# LPCB234_-_CAN.net
KiCad netlist of a schematic drawn in Altium Designer
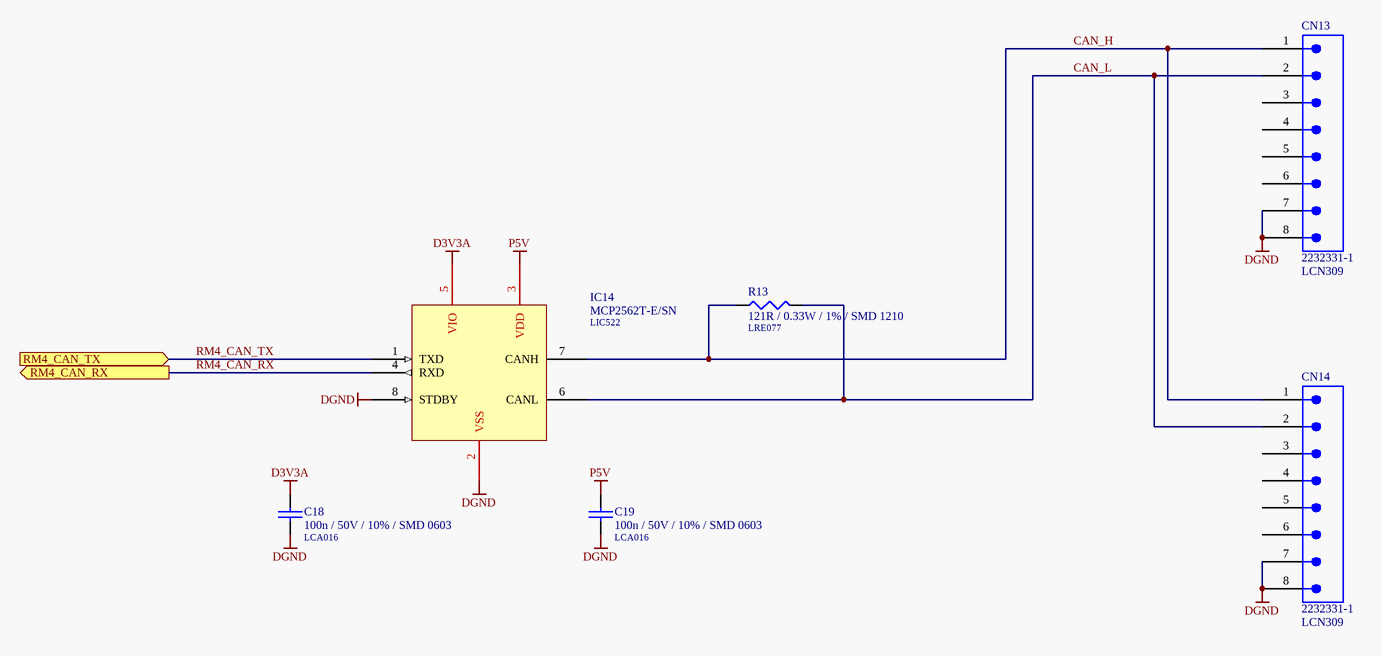
[diagram p0: LPCB234 - CAN.SchDoc]

(export (version "E")
  (design (tool "Eeschema 10.0.6"))
  (components
    (comp (ref "C18")
      (value "100n / 50V / 10% / SMD 0603")
      (footprint "LFP011__CC1608-0603-IPC7351_B")
      (description "Capacitor, Ceramic Chip, 100nF (0.1uF), 50V, 5%, SMD 0603 [LCA016]")
      (fields (field (name "LDL_NUMBER") "LCA016"))
      (libsource (lib "LDL_Capacitors") (part "100n / 50V / 10% / SMD 0603"))
    )
    (comp (ref "C19")
      (value "100n / 50V / 10% / SMD 0603")
      (footprint "LFP011__CC1608-0603-IPC7351_B")
      (description "Capacitor, Ceramic Chip, 100nF (0.1uF), 50V, 5%, SMD 0603 [LCA016]")
      (fields (field (name "LDL_NUMBER") "LCA016"))
      (libsource (lib "LDL_Capacitors") (part "100n / 50V / 10% / SMD 0603"))
    )
    (comp (ref "CN13")
      (value "2232331-1")
      (footprint "2232331-1")
      (description "Connector, M12 8 Way, PCB Mount")
      (fields (field (name "LDL_NUMBER") "LCN309"))
      (libsource (lib "LDL_Connectors") (part "2232331-1"))
    )
    (comp (ref "CN14")
      (value "2232331-1")
      (footprint "2232331-1")
      (description "Connector, M12 8 Way, PCB Mount")
      (fields (field (name "LDL_NUMBER") "LCN309"))
      (libsource (lib "LDL_Connectors") (part "2232331-1"))
    )
    (comp (ref "IC14")
      (value "MCP2562T-E/SN")
      (footprint "LFP017__SO-G8/Y1.9")
      (description "IC, High Speed CAN Transceiver, SMD SOIC8 [LIC522]")
      (fields (field (name "LDL_NUMBER") "LIC522"))
      (libsource (lib "LDL_Semiconductors") (part "MCP2562T-E/SN"))
    )
    (comp (ref "R13")
      (value "121R / 0.33W / 1% / SMD 1210")
      (footprint "LFP028__CR3225-1210")
      (description "Resistor, Ceramic Chip, 121R, 0.33W, 1%, SMD 1210 [LRE077]")
      (fields (field (name "LDL_NUMBER") "LRE077"))
      (libsource (lib "LDL_Resistors") (part "121R / 0.33W / 1% / SMD 1210"))
    )
  )
  (nets
    (net (code "1") (name "/CAN_H") (class "Default")
      (node (ref "CN13") (pin "1") (pinfunction "1_1") (pintype "passive"))
      (node (ref "CN14") (pin "1") (pinfunction "1_1") (pintype "passive"))
      (node (ref "IC14") (pin "7") (pinfunction "CANH_7") (pintype "passive"))
      (node (ref "R13") (pin "1") (pintype "passive"))
    )
    (net (code "2") (name "/CAN_L") (class "Default")
      (node (ref "CN13") (pin "2") (pinfunction "2_2") (pintype "passive"))
      (node (ref "CN14") (pin "2") (pinfunction "2_2") (pintype "passive"))
      (node (ref "IC14") (pin "6") (pinfunction "CANL_6") (pintype "passive"))
      (node (ref "R13") (pin "2") (pintype "passive"))
    )
    (net (code "3") (name "/RM4_CAN_RX") (class "Default")
      (node (ref "IC14") (pin "4") (pinfunction "RXD_4") (pintype "output"))
    )
    (net (code "4") (name "/RM4_CAN_TX") (class "Default")
      (node (ref "IC14") (pin "1") (pinfunction "TXD_1") (pintype "input"))
    )
    (net (code "5") (name "D3V3A") (class "Default")
      (node (ref "C18") (pin "1") (pintype "passive"))
      (node (ref "IC14") (pin "5") (pinfunction "VIO_5") (pintype "power_in"))
    )
    (net (code "6") (name "DGND") (class "Default")
      (node (ref "C18") (pin "2") (pintype "passive"))
      (node (ref "C19") (pin "2") (pintype "passive"))
      (node (ref "CN13") (pin "7") (pinfunction "7_7") (pintype "passive"))
      (node (ref "CN13") (pin "8") (pinfunction "8_8") (pintype "passive"))
      (node (ref "CN14") (pin "7") (pinfunction "7_7") (pintype "passive"))
      (node (ref "CN14") (pin "8") (pinfunction "8_8") (pintype "passive"))
      (node (ref "IC14") (pin "2") (pinfunction "VSS_2") (pintype "passive"))
      (node (ref "IC14") (pin "8") (pinfunction "STDBY_8") (pintype "input"))
    )
    (net (code "7") (name "P5V") (class "Default")
      (node (ref "C19") (pin "1") (pintype "passive"))
      (node (ref "IC14") (pin "3") (pinfunction "VDD_3") (pintype "passive"))
    )
    (net (code "8") (name "unconnected-(CN13-Pad3)") (class "Default")
      (node (ref "CN13") (pin "3") (pinfunction "3_3") (pintype "passive"))
    )
    (net (code "9") (name "unconnected-(CN13-Pad4)") (class "Default")
      (node (ref "CN13") (pin "4") (pinfunction "4_4") (pintype "passive"))
    )
    (net (code "10") (name "unconnected-(CN13-Pad5)") (class "Default")
      (node (ref "CN13") (pin "5") (pinfunction "5_5") (pintype "passive"))
    )
    (net (code "11") (name "unconnected-(CN13-Pad6)") (class "Default")
      (node (ref "CN13") (pin "6") (pinfunction "6_6") (pintype "passive"))
    )
    (net (code "12") (name "unconnected-(CN14-Pad3)") (class "Default")
      (node (ref "CN14") (pin "3") (pinfunction "3_3") (pintype "passive"))
    )
    (net (code "13") (name "unconnected-(CN14-Pad4)") (class "Default")
      (node (ref "CN14") (pin "4") (pinfunction "4_4") (pintype "passive"))
    )
    (net (code "14") (name "unconnected-(CN14-Pad5)") (class "Default")
      (node (ref "CN14") (pin "5") (pinfunction "5_5") (pintype "passive"))
    )
    (net (code "15") (name "unconnected-(CN14-Pad6)") (class "Default")
      (node (ref "CN14") (pin "6") (pinfunction "6_6") (pintype "passive"))
    )
  )
)
